# DC_Volt_Sense.net
KiCad netlist of a schematic drawn in Altium Designer
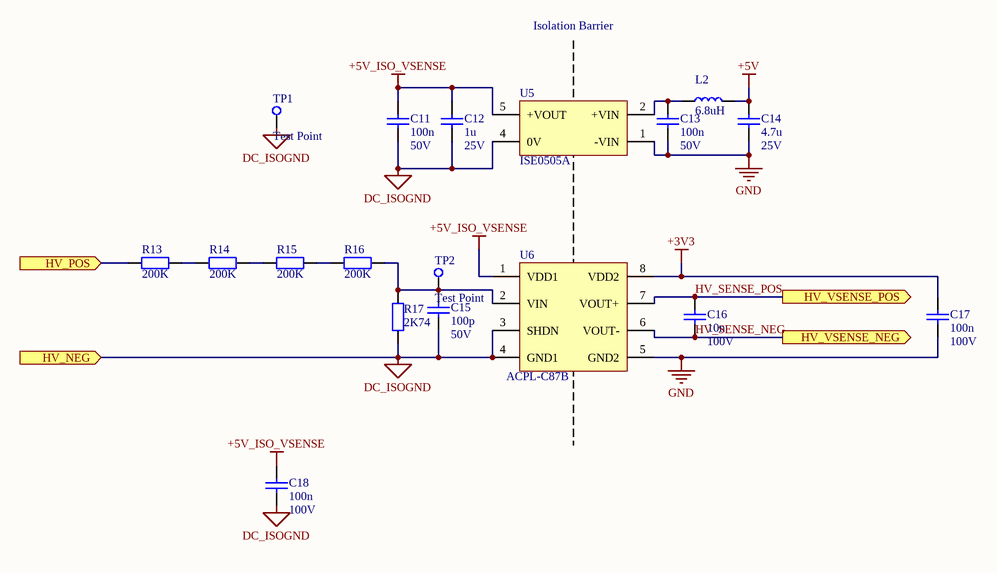
[diagram p0: DC_Volt_Sense.SchDoc]

(export (version "E")
  (design (tool "Eeschema 10.0.6"))
  (components
    (comp (ref "C11")
      (value "100n")
      (footprint "CAP 0603/1608")
      (description "CAP CER 0.1UF 50V X7R 0603")
      (fields
        (field (name "VOLTAGE - RATED") "50V")
        (field (name "PART NUMBER") "GCM188R71H104KA57D")
        (field (name "MANUFACTURER") "Murata Electronics North America")
      )
      (libsource (lib "electric_racing_lib") (part "Capacitor"))
    )
    (comp (ref "C12")
      (value "1u")
      (footprint "CAP 0603/1608")
      (description "CAP CER 1UF 25V X7R 0603")
      (fields
        (field (name "VOLTAGE - RATED") "25V")
        (field (name "PART NUMBER") "CL10B105KA8NNNC")
        (field (name "MANUFACTURER") "Samsung Electro-Mechanics")
      )
      (libsource (lib "electric_racing_lib") (part "Capacitor"))
    )
    (comp (ref "C13")
      (value "100n")
      (footprint "CAP 0603/1608")
      (description "CAP CER 0.1UF 50V X7R 0603")
      (fields
        (field (name "VOLTAGE - RATED") "50V")
        (field (name "PART NUMBER") "GCM188R71H104KA57D")
        (field (name "MANUFACTURER") "Murata Electronics North America")
      )
      (libsource (lib "electric_racing_lib") (part "Capacitor"))
    )
    (comp (ref "C14")
      (value "4.7u")
      (footprint "CAP 0603/1608")
      (description "CAP CER 4.7UF 25V X6S 0603")
      (fields
        (field (name "VOLTAGE - RATED") "25V")
        (field (name "PART NUMBER") "GRM188C81E475KE11D")
        (field (name "MANUFACTURER") "Murata Electronics North America")
      )
      (libsource (lib "electric_racing_lib") (part "Capacitor"))
    )
    (comp (ref "C15")
      (value "100p")
      (footprint "CAP 0603/1608")
      (description "CAP CER 100PF 50V C0G/NP0 0603")
      (fields
        (field (name "VOLTAGE - RATED") "50V")
        (field (name "PART NUMBER") "C0603C101J5GACTU")
        (field (name "MANUFACTURER") "KEMET")
      )
      (libsource (lib "electric_racing_lib") (part "Capacitor"))
    )
    (comp (ref "C16")
      (value "10n")
      (footprint "CAP 0603/1608")
      (description "CAP CER 10000PF 100V X7R 0603")
      (fields
        (field (name "VOLTAGE - RATED") "100V")
        (field (name "PART NUMBER") "GCM188R72A103KA37D")
        (field (name "MANUFACTURER") "Murata Electronics North America")
      )
      (libsource (lib "electric_racing_lib") (part "Capacitor"))
    )
    (comp (ref "C17")
      (value "100n")
      (footprint "CAP 0805/2012 - 1.4MM")
      (description "CAP CER 0.1UF 100V X7R 0805")
      (fields
        (field (name "VOLTAGE - RATED") "100V")
        (field (name "PART NUMBER") "GCM21BR72A104KA37L")
        (field (name "MANUFACTURER") "Murata Electronics North America")
      )
      (libsource (lib "electric_racing_lib") (part "Capacitor"))
    )
    (comp (ref "C18")
      (value "100n")
      (footprint "CAP 0805/2012 - 1.4MM")
      (description "CAP CER 0.1UF 100V X7R 0805")
      (fields
        (field (name "VOLTAGE - RATED") "100V")
        (field (name "PART NUMBER") "GCM21BR72A104KA37L")
        (field (name "MANUFACTURER") "Murata Electronics North America")
      )
      (libsource (lib "electric_racing_lib") (part "Capacitor"))
    )
    (comp (ref "L2")
      (value "6.8uH")
      (footprint "1210L")
      (fields
        (field (name "PART NUMBER") "MLZ2012N6R8LTD25")
        (field (name "MANUFACTURER") "TDK Corporation")
        (field (name "DIGI-KEY PART NUMBER") "445-16384-1-ND")
      )
      (libsource (lib "Database_library") (part "Inductor"))
    )
    (comp (ref "R13")
      (value "200K")
      (footprint "RES 1206/3216")
      (description "RES SMD 200K OHM 1% 1/4W 1206")
      (fields (field (name "PART NUMBER") "RC1206FR-07200KL") (field (name "TOLERANCE") "±1%"))
      (libsource (lib "electric_racing_lib") (part "Resistor"))
    )
    (comp (ref "R14")
      (value "200K")
      (footprint "RES 1206/3216")
      (description "RES SMD 200K OHM 1% 1/4W 1206")
      (fields (field (name "PART NUMBER") "RC1206FR-07200KL") (field (name "TOLERANCE") "±1%"))
      (libsource (lib "electric_racing_lib") (part "Resistor"))
    )
    (comp (ref "R15")
      (value "200K")
      (footprint "RES 1206/3216")
      (description "RES SMD 200K OHM 1% 1/4W 1206")
      (fields (field (name "PART NUMBER") "RC1206FR-07200KL") (field (name "TOLERANCE") "±1%"))
      (libsource (lib "electric_racing_lib") (part "Resistor"))
    )
    (comp (ref "R16")
      (value "200K")
      (footprint "RES 1206/3216")
      (description "RES SMD 200K OHM 1% 1/4W 1206")
      (fields (field (name "PART NUMBER") "RC1206FR-07200KL") (field (name "TOLERANCE") "±1%"))
      (libsource (lib "electric_racing_lib") (part "Resistor"))
    )
    (comp (ref "R17")
      (value "2K74")
      (footprint "RES 1206/3216")
      (description "RES SMD 2.74K OHM 1% 1/4W 1206")
      (fields (field (name "PART NUMBER") "RC1206FR-072K74L") (field (name "TOLERANCE") "±1%"))
      (libsource (lib "") (part "Resistor_1"))
    )
    (comp (ref "TP1")
      (value "Test Point")
      (footprint "RCT-0C")
      (description "0805 PROBE PAD")
      (fields (field (name "PART NUMBER") "RCT-0C") (field (name "DIGI-KEY PART NUMBER") "A106144CT-ND"))
      (libsource (lib "electric_racing_lib") (part "Test Point"))
    )
    (comp (ref "TP2")
      (value "Test Point")
      (footprint "RCT-0C")
      (description "0805 PROBE PAD")
      (fields (field (name "PART NUMBER") "RCT-0C") (field (name "DIGI-KEY PART NUMBER") "A106144CT-ND"))
      (libsource (lib "electric_racing_lib") (part "Test Point"))
    )
    (comp (ref "U5")
      (value "ISE0505A")
      (footprint "XP ISE 8-SMD")
      (description "Isolated Module DC DC Converter 1 Output 5V 200mA 4.5V - 5.5V Input")
      (fields (field (name "MANUFACTURER") "XP Power") (field (name "DIGI-KEY PART NUMBER") "1470-2945-1-ND"))
      (libsource (lib "electric_racing_lib") (part "XP POWER ISE"))
    )
    (comp (ref "U6")
      (value "ACPL-C87B")
      (footprint "Broadcom SSO-8")
      (description "Isolation Amplifier 1 Circuit Differential 8-SO")
      (fields (field (name "MANUFACTURER") "Broadcom") (field (name "DIGI-KEY PART NUMBER") "516-2579-5-ND"))
      (libsource (lib "electric_racing_lib") (part "ACPL-C87B"))
    )
  )
  (nets
    (net (code "1") (name "+3V3") (class "Default")
      (node (ref "C17") (pin "2") (pinfunction "2_2") (pintype "passive"))
      (node (ref "U6") (pin "8") (pinfunction "VDD2_8") (pintype "passive"))
    )
    (net (code "2") (name "+5V") (class "Default")
      (node (ref "C14") (pin "2") (pinfunction "2_2") (pintype "passive"))
      (node (ref "L2") (pin "1") (pinfunction "1_1") (pintype "passive"))
    )
    (net (code "3") (name "+5V_ISO_VSENSE") (class "Default")
      (node (ref "C11") (pin "2") (pinfunction "2_2") (pintype "passive"))
      (node (ref "C12") (pin "2") (pinfunction "2_2") (pintype "passive"))
      (node (ref "C18") (pin "2") (pinfunction "2_2") (pintype "passive"))
      (node (ref "U5") (pin "5") (pinfunction "+VOUT_5") (pintype "passive"))
      (node (ref "U6") (pin "1") (pinfunction "VDD1_1") (pintype "passive"))
    )
    (net (code "4") (name "/HV_POS") (class "Default")
      (node (ref "R13") (pin "1") (pinfunction "1_1") (pintype "passive"))
    )
    (net (code "5") (name "/HV_SENSE_NEG") (class "Default")
      (node (ref "C16") (pin "1") (pinfunction "1_1") (pintype "passive"))
      (node (ref "U6") (pin "6") (pinfunction "VOUT-_6") (pintype "passive"))
    )
    (net (code "6") (name "/HV_SENSE_POS") (class "Default")
      (node (ref "C16") (pin "2") (pinfunction "2_2") (pintype "passive"))
      (node (ref "U6") (pin "7") (pinfunction "VOUT+_7") (pintype "passive"))
    )
    (net (code "7") (name "DC_ISOGND") (class "Default")
      (node (ref "C11") (pin "1") (pinfunction "1_1") (pintype "passive"))
      (node (ref "C12") (pin "1") (pinfunction "1_1") (pintype "passive"))
      (node (ref "C15") (pin "1") (pinfunction "1_1") (pintype "passive"))
      (node (ref "C18") (pin "1") (pinfunction "1_1") (pintype "passive"))
      (node (ref "R17") (pin "1") (pinfunction "1_1") (pintype "passive"))
      (node (ref "TP1") (pin "1") (pinfunction "TP_1") (pintype "passive"))
      (node (ref "U5") (pin "4") (pinfunction "0V_4") (pintype "passive"))
      (node (ref "U6") (pin "3") (pinfunction "SHDN_3") (pintype "passive"))
      (node (ref "U6") (pin "4") (pinfunction "GND1_4") (pintype "passive"))
    )
    (net (code "8") (name "GND") (class "Default")
      (node (ref "C13") (pin "2") (pinfunction "2_2") (pintype "passive"))
      (node (ref "C14") (pin "1") (pinfunction "1_1") (pintype "passive"))
      (node (ref "C17") (pin "1") (pinfunction "1_1") (pintype "passive"))
      (node (ref "U5") (pin "1") (pinfunction "-VIN_1") (pintype "passive"))
      (node (ref "U6") (pin "5") (pinfunction "GND2_5") (pintype "passive"))
    )
    (net (code "9") (name "Net-(R13-Pad2)") (class "Default")
      (node (ref "R13") (pin "2") (pinfunction "2_2") (pintype "passive"))
      (node (ref "R14") (pin "1") (pinfunction "1_1") (pintype "passive"))
    )
    (net (code "10") (name "Net-(R14-Pad2)") (class "Default")
      (node (ref "R14") (pin "2") (pinfunction "2_2") (pintype "passive"))
      (node (ref "R15") (pin "1") (pinfunction "1_1") (pintype "passive"))
    )
    (net (code "11") (name "Net-(R15-Pad2)") (class "Default")
      (node (ref "R15") (pin "2") (pinfunction "2_2") (pintype "passive"))
      (node (ref "R16") (pin "1") (pinfunction "1_1") (pintype "passive"))
    )
    (net (code "12") (name "Net-(TP2-TP)") (class "Default")
      (node (ref "C15") (pin "2") (pinfunction "2_2") (pintype "passive"))
      (node (ref "R16") (pin "2") (pinfunction "2_2") (pintype "passive"))
      (node (ref "R17") (pin "2") (pinfunction "2_2") (pintype "passive"))
      (node (ref "TP2") (pin "1") (pinfunction "TP_1") (pintype "passive"))
      (node (ref "U6") (pin "2") (pinfunction "VIN_2") (pintype "passive"))
    )
    (net (code "13") (name "Net-(U5-+VIN)") (class "Default")
      (node (ref "C13") (pin "1") (pinfunction "1_1") (pintype "passive"))
      (node (ref "L2") (pin "2") (pinfunction "2_2") (pintype "passive"))
      (node (ref "U5") (pin "2") (pinfunction "+VIN_2") (pintype "passive"))
    )
  )
)
